# final-project.net
KiCad netlist of a schematic drawn in Altium Designer
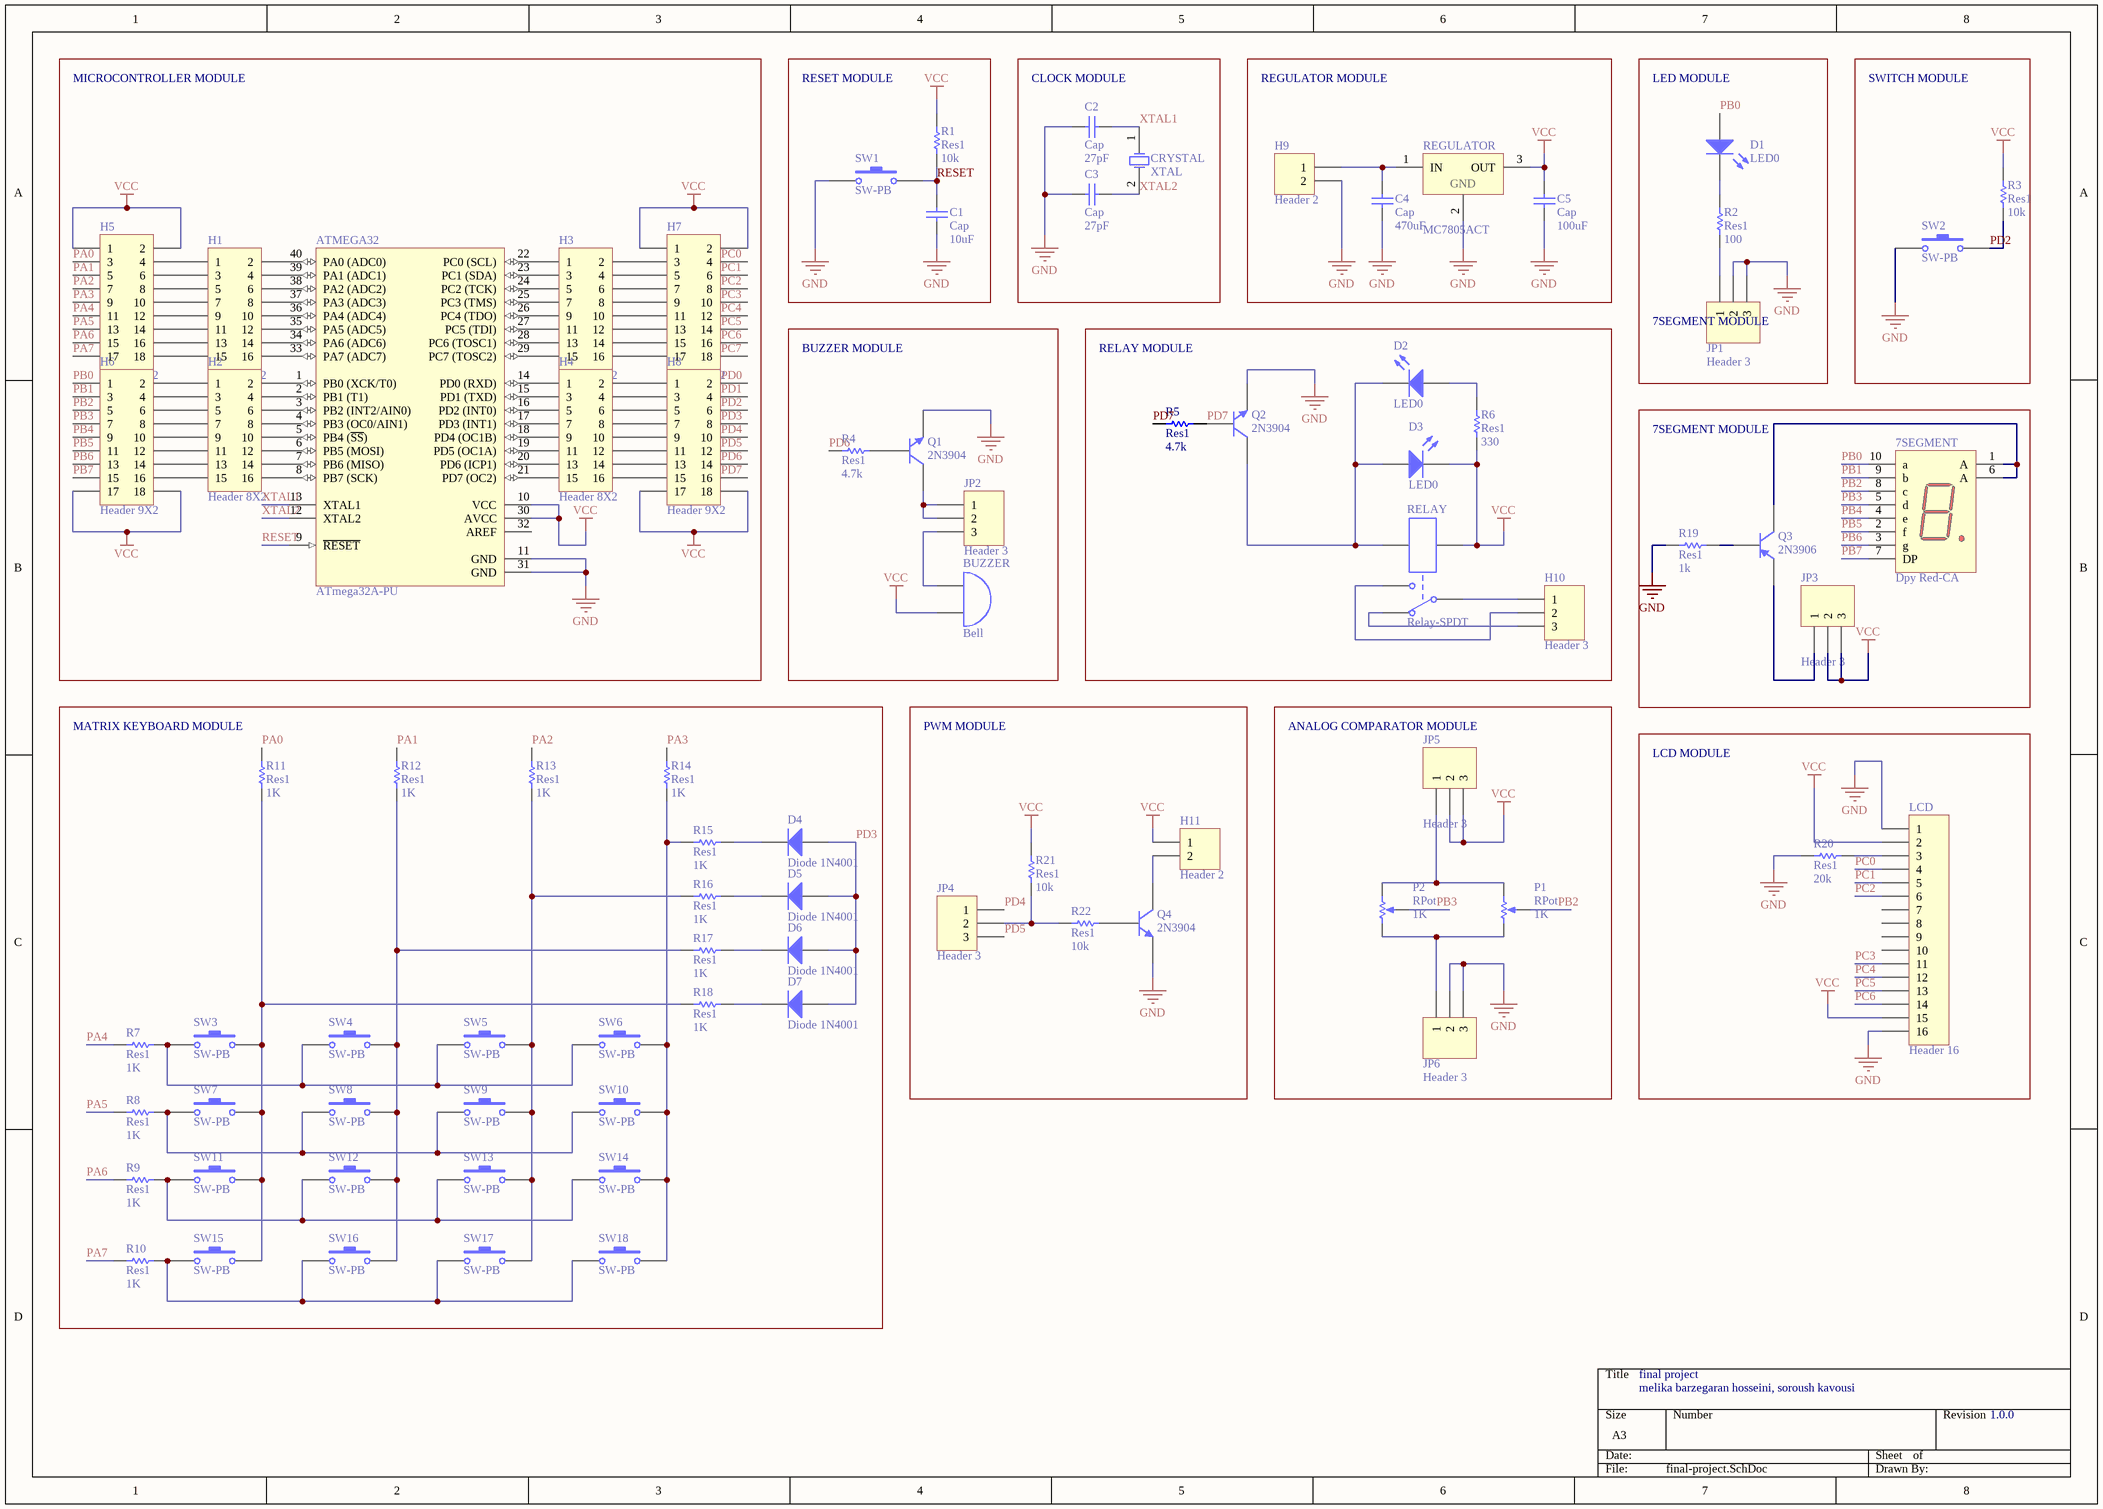
[diagram p0: final-project.SchDoc]

(export (version "E")
  (design (tool "Eeschema 10.0.6"))
  (components
    (comp (ref "7SEGMENT")
      (value "Dpy Red-CA")
      (footprint "LEDDIP-10/C5.08RHD")
      (description "7.62 mm Black Surface HER 7-Segment Display: CA, RH DP")
      (libsource (lib "Miscellaneous Devices") (part "Dpy Red-CA"))
    )
    (comp (ref "ATMEGA32")
      (value "ATmega32A-PU")
      (footprint "40P6")
      (libsource (lib "Atmel Microcontroller 8-Bit megaAVR") (part "ATmega32A-PU"))
    )
    (comp (ref "BUZZER")
      (value "Bell")
      (footprint "PIN2")
      (description "Electrical Bell")
      (libsource (lib "Miscellaneous Devices") (part "Bell"))
    )
    (comp (ref "C1")
      (value "Cap")
      (footprint "RAD-0.3")
      (description "Capacitor")
      (fields (field (name "ALTIUM_VALUE") "10uF"))
      (libsource (lib "Miscellaneous Devices") (part "Cap"))
    )
    (comp (ref "C2")
      (value "Cap")
      (footprint "RAD-0.3")
      (description "Capacitor")
      (fields (field (name "ALTIUM_VALUE") "27pF"))
      (libsource (lib "Miscellaneous Devices") (part "Cap"))
    )
    (comp (ref "C3")
      (value "Cap")
      (footprint "RAD-0.3")
      (description "Capacitor")
      (fields (field (name "ALTIUM_VALUE") "27pF"))
      (libsource (lib "Miscellaneous Devices") (part "Cap"))
    )
    (comp (ref "C4")
      (value "Cap")
      (footprint "RAD-0.3")
      (description "Capacitor")
      (fields (field (name "ALTIUM_VALUE") "470uF"))
      (libsource (lib "Miscellaneous Devices") (part "Cap"))
    )
    (comp (ref "C5")
      (value "Cap")
      (footprint "RAD-0.3")
      (description "Capacitor")
      (fields (field (name "ALTIUM_VALUE") "100uF"))
      (libsource (lib "Miscellaneous Devices") (part "Cap"))
    )
    (comp (ref "CRYSTAL")
      (value "XTAL")
      (footprint "BCY-W2/D3.1")
      (description "Crystal Oscillator")
      (libsource (lib "Miscellaneous Devices") (part "XTAL"))
    )
    (comp (ref "D1")
      (value "LED0")
      (footprint "RB5-10.5")
      (description "Typical INFRARED GaAs LED")
      (libsource (lib "Miscellaneous Devices") (part "LED0"))
    )
    (comp (ref "D2")
      (value "LED0")
      (footprint "RB5-10.5")
      (description "Typical INFRARED GaAs LED")
      (libsource (lib "Miscellaneous Devices") (part "LED0"))
    )
    (comp (ref "D3")
      (value "LED0")
      (footprint "RB5-10.5")
      (description "Typical INFRARED GaAs LED")
      (libsource (lib "Miscellaneous Devices") (part "LED0"))
    )
    (comp (ref "D4")
      (value "Diode 1N4001")
      (footprint "DIO10.46-5.3x2.8")
      (description "1 Amp General Purpose Rectifier")
      (libsource (lib "Miscellaneous Devices") (part "Diode 1N4001"))
    )
    (comp (ref "D5")
      (value "Diode 1N4001")
      (footprint "DIO10.46-5.3x2.8")
      (description "1 Amp General Purpose Rectifier")
      (libsource (lib "Miscellaneous Devices") (part "Diode 1N4001"))
    )
    (comp (ref "D6")
      (value "Diode 1N4001")
      (footprint "DIO10.46-5.3x2.8")
      (description "1 Amp General Purpose Rectifier")
      (libsource (lib "Miscellaneous Devices") (part "Diode 1N4001"))
    )
    (comp (ref "D7")
      (value "Diode 1N4001")
      (footprint "DIO10.46-5.3x2.8")
      (description "1 Amp General Purpose Rectifier")
      (libsource (lib "Miscellaneous Devices") (part "Diode 1N4001"))
    )
    (comp (ref "H1")
      (value "Header 8X2")
      (footprint "HDR1X8")
      (description "Header, 8-Pin, Dual row")
      (libsource (lib "Miscellaneous Connectors") (part "Header 8X2"))
    )
    (comp (ref "H2")
      (value "Header 8X2")
      (footprint "HDR1X8")
      (description "Header, 8-Pin, Dual row")
      (libsource (lib "Miscellaneous Connectors") (part "Header 8X2"))
    )
    (comp (ref "H3")
      (value "Header 8X2")
      (footprint "HDR1X8")
      (description "Header, 8-Pin, Dual row")
      (libsource (lib "Miscellaneous Connectors") (part "Header 8X2"))
    )
    (comp (ref "H4")
      (value "Header 8X2")
      (footprint "HDR1X8")
      (description "Header, 8-Pin, Dual row")
      (libsource (lib "Miscellaneous Connectors") (part "Header 8X2"))
    )
    (comp (ref "H5")
      (value "Header 9X2")
      (footprint "HDR1X9")
      (description "Header, 9-Pin, Dual row")
      (libsource (lib "Miscellaneous Connectors") (part "Header 9X2"))
    )
    (comp (ref "H6")
      (value "Header 9X2")
      (footprint "HDR1X9")
      (description "Header, 9-Pin, Dual row")
      (libsource (lib "Miscellaneous Connectors") (part "Header 9X2"))
    )
    (comp (ref "H7")
      (value "Header 9X2")
      (footprint "HDR1X9")
      (description "Header, 9-Pin, Dual row")
      (libsource (lib "Miscellaneous Connectors") (part "Header 9X2"))
    )
    (comp (ref "H8")
      (value "Header 9X2")
      (footprint "HDR1X9")
      (description "Header, 9-Pin, Dual row")
      (libsource (lib "Miscellaneous Connectors") (part "Header 9X2"))
    )
    (comp (ref "H9")
      (value "Header 2")
      (footprint "HDR1X2")
      (description "Header, 2-Pin")
      (libsource (lib "") (part "Header 2_1"))
    )
    (comp (ref "H10")
      (value "Header 3")
      (footprint "HDR1X3")
      (description "Header, 3-Pin")
      (libsource (lib "") (part "Header 3_2"))
    )
    (comp (ref "H11")
      (value "Header 2")
      (footprint "HDR1X2")
      (description "Header, 2-Pin")
      (libsource (lib "Miscellaneous Connectors") (part "Header 2"))
    )
    (comp (ref "JP1")
      (value "Header 3")
      (footprint "HDR1X3")
      (description "Header, 3-Pin")
      (libsource (lib "Miscellaneous Connectors") (part "Header 3"))
    )
    (comp (ref "JP2")
      (value "Header 3")
      (footprint "HDR1X3")
      (description "Header, 3-Pin")
      (libsource (lib "") (part "Header 3_2"))
    )
    (comp (ref "JP3")
      (value "Header 3")
      (footprint "HDR1X3")
      (description "Header, 3-Pin")
      (libsource (lib "") (part "Header 3_1"))
    )
    (comp (ref "JP4")
      (value "Header 3")
      (footprint "HDR1X3")
      (description "Header, 3-Pin")
      (libsource (lib "") (part "Header 3_3"))
    )
    (comp (ref "JP5")
      (value "Header 3")
      (footprint "HDR1X3")
      (description "Header, 3-Pin")
      (libsource (lib "") (part "Header 3_1"))
    )
    (comp (ref "JP6")
      (value "Header 3")
      (footprint "HDR1X3")
      (description "Header, 3-Pin")
      (libsource (lib "Miscellaneous Connectors") (part "Header 3"))
    )
    (comp (ref "LCD")
      (value "Header 16")
      (footprint "HDR1X16")
      (description "Header, 16-Pin")
      (libsource (lib "Miscellaneous Connectors") (part "Header 16"))
    )
    (comp (ref "P1")
      (value "RPot")
      (footprint "VR5")
      (description "Potentiometer")
      (fields (field (name "ALTIUM_VALUE") "1K"))
      (libsource (lib "Miscellaneous Devices") (part "RPot"))
    )
    (comp (ref "P2")
      (value "RPot")
      (footprint "VR5")
      (description "Potentiometer")
      (fields (field (name "ALTIUM_VALUE") "1K"))
      (libsource (lib "Miscellaneous Devices") (part "RPot"))
    )
    (comp (ref "Q1")
      (value "2N3904")
      (footprint "HDR1X3")
      (description "NPN General Purpose Amplifier")
      (libsource (lib "Miscellaneous Devices") (part "2N3904"))
    )
    (comp (ref "Q2")
      (value "2N3904")
      (footprint "HDR1X3")
      (description "NPN General Purpose Amplifier")
      (libsource (lib "Miscellaneous Devices") (part "2N3904"))
    )
    (comp (ref "Q3")
      (value "2N3906")
      (footprint "HDR1X3")
      (description "PNP General Purpose Amplifier")
      (libsource (lib "Miscellaneous Devices") (part "2N3906"))
    )
    (comp (ref "Q4")
      (value "2N3904")
      (footprint "HDR1X3")
      (description "NPN General Purpose Amplifier")
      (libsource (lib "Miscellaneous Devices") (part "2N3904"))
    )
    (comp (ref "R1")
      (value "Res1")
      (footprint "AXIAL-0.3")
      (description "Resistor")
      (fields (field (name "ALTIUM_VALUE") "10k"))
      (libsource (lib "Miscellaneous Devices") (part "Res1"))
    )
    (comp (ref "R2")
      (value "Res1")
      (footprint "AXIAL-0.3")
      (description "Resistor")
      (fields (field (name "ALTIUM_VALUE") "100"))
      (libsource (lib "Miscellaneous Devices") (part "Res1"))
    )
    (comp (ref "R3")
      (value "Res1")
      (footprint "AXIAL-0.3")
      (description "Resistor")
      (fields (field (name "ALTIUM_VALUE") "10k"))
      (libsource (lib "Miscellaneous Devices") (part "Res1"))
    )
    (comp (ref "R4")
      (value "Res1")
      (footprint "AXIAL-0.3")
      (description "Resistor")
      (fields (field (name "ALTIUM_VALUE") "4.7k"))
      (libsource (lib "Miscellaneous Devices") (part "Res1"))
    )
    (comp (ref "R5")
      (value "Res1")
      (footprint "AXIAL-0.3")
      (description "Resistor")
      (fields (field (name "ALTIUM_VALUE") "4.7k"))
      (libsource (lib "Miscellaneous Devices") (part "Res1"))
    )
    (comp (ref "R6")
      (value "Res1")
      (footprint "AXIAL-0.3")
      (description "Resistor")
      (fields (field (name "ALTIUM_VALUE") "330"))
      (libsource (lib "Miscellaneous Devices") (part "Res1"))
    )
    (comp (ref "R7")
      (value "Res1")
      (footprint "AXIAL-0.3")
      (description "Resistor")
      (fields (field (name "ALTIUM_VALUE") "1K"))
      (libsource (lib "Miscellaneous Devices") (part "Res1"))
    )
    (comp (ref "R8")
      (value "Res1")
      (footprint "AXIAL-0.3")
      (description "Resistor")
      (fields (field (name "ALTIUM_VALUE") "1K"))
      (libsource (lib "Miscellaneous Devices") (part "Res1"))
    )
    (comp (ref "R9")
      (value "Res1")
      (footprint "AXIAL-0.3")
      (description "Resistor")
      (fields (field (name "ALTIUM_VALUE") "1K"))
      (libsource (lib "Miscellaneous Devices") (part "Res1"))
    )
    (comp (ref "R10")
      (value "Res1")
      (footprint "AXIAL-0.3")
      (description "Resistor")
      (fields (field (name "ALTIUM_VALUE") "1K"))
      (libsource (lib "Miscellaneous Devices") (part "Res1"))
    )
    (comp (ref "R11")
      (value "Res1")
      (footprint "AXIAL-0.3")
      (description "Resistor")
      (fields (field (name "ALTIUM_VALUE") "1K"))
      (libsource (lib "Miscellaneous Devices") (part "Res1"))
    )
    (comp (ref "R12")
      (value "Res1")
      (footprint "AXIAL-0.3")
      (description "Resistor")
      (fields (field (name "ALTIUM_VALUE") "1K"))
      (libsource (lib "Miscellaneous Devices") (part "Res1"))
    )
    (comp (ref "R13")
      (value "Res1")
      (footprint "AXIAL-0.3")
      (description "Resistor")
      (fields (field (name "ALTIUM_VALUE") "1K"))
      (libsource (lib "Miscellaneous Devices") (part "Res1"))
    )
    (comp (ref "R14")
      (value "Res1")
      (footprint "AXIAL-0.3")
      (description "Resistor")
      (fields (field (name "ALTIUM_VALUE") "1K"))
      (libsource (lib "Miscellaneous Devices") (part "Res1"))
    )
    (comp (ref "R15")
      (value "Res1")
      (footprint "AXIAL-0.3")
      (description "Resistor")
      (fields (field (name "ALTIUM_VALUE") "1K"))
      (libsource (lib "Miscellaneous Devices") (part "Res1"))
    )
    (comp (ref "R16")
      (value "Res1")
      (footprint "AXIAL-0.3")
      (description "Resistor")
      (fields (field (name "ALTIUM_VALUE") "1K"))
      (libsource (lib "Miscellaneous Devices") (part "Res1"))
    )
    (comp (ref "R17")
      (value "Res1")
      (footprint "AXIAL-0.3")
      (description "Resistor")
      (fields (field (name "ALTIUM_VALUE") "1K"))
      (libsource (lib "Miscellaneous Devices") (part "Res1"))
    )
    (comp (ref "R18")
      (value "Res1")
      (footprint "AXIAL-0.3")
      (description "Resistor")
      (fields (field (name "ALTIUM_VALUE") "1K"))
      (libsource (lib "Miscellaneous Devices") (part "Res1"))
    )
    (comp (ref "R19")
      (value "Res1")
      (footprint "AXIAL-0.3")
      (description "Resistor")
      (fields (field (name "ALTIUM_VALUE") "1k"))
      (libsource (lib "Miscellaneous Devices") (part "Res1"))
    )
    (comp (ref "R20")
      (value "Res1")
      (footprint "AXIAL-0.3")
      (description "Resistor")
      (fields (field (name "ALTIUM_VALUE") "20k"))
      (libsource (lib "Miscellaneous Devices") (part "Res1"))
    )
    (comp (ref "R21")
      (value "Res1")
      (footprint "AXIAL-0.3")
      (description "Resistor")
      (fields (field (name "ALTIUM_VALUE") "10k"))
      (libsource (lib "Miscellaneous Devices") (part "Res1"))
    )
    (comp (ref "R22")
      (value "Res1")
      (footprint "AXIAL-0.3")
      (description "Resistor")
      (fields (field (name "ALTIUM_VALUE") "10k"))
      (libsource (lib "Miscellaneous Devices") (part "Res1"))
    )
    (comp (ref "REGULATOR")
      (value "MC7805ACT")
      (footprint "221A-04")
      (description "3-Terminal Positive Fixed Voltage Regulator")
      (libsource (lib "Motorola Power Mgt Voltage Regulator") (part "MC7805ACT"))
    )
    (comp (ref "RELAY")
      (value "Relay-SPDT")
      (footprint "DIP-P5/X1.65")
      (description "Single-Pole Dual-Throw Relay")
      (libsource (lib "Miscellaneous Devices") (part "Relay-SPDT"))
    )
    (comp (ref "SW1")
      (value "SW-PB")
      (footprint "SPST-2")
      (description "Switch")
      (libsource (lib "Miscellaneous Devices") (part "SW-PB"))
    )
    (comp (ref "SW2")
      (value "SW-PB")
      (footprint "SPST-2")
      (description "Switch")
      (libsource (lib "Miscellaneous Devices") (part "SW-PB"))
    )
    (comp (ref "SW3")
      (value "SW-PB")
      (footprint "SPST-2")
      (description "Switch")
      (libsource (lib "Miscellaneous Devices") (part "SW-PB"))
    )
    (comp (ref "SW4")
      (value "SW-PB")
      (footprint "SPST-2")
      (description "Switch")
      (libsource (lib "Miscellaneous Devices") (part "SW-PB"))
    )
    (comp (ref "SW5")
      (value "SW-PB")
      (footprint "SPST-2")
      (description "Switch")
      (libsource (lib "Miscellaneous Devices") (part "SW-PB"))
    )
    (comp (ref "SW6")
      (value "SW-PB")
      (footprint "SPST-2")
      (description "Switch")
      (libsource (lib "Miscellaneous Devices") (part "SW-PB"))
    )
    (comp (ref "SW7")
      (value "SW-PB")
      (footprint "SPST-2")
      (description "Switch")
      (libsource (lib "Miscellaneous Devices") (part "SW-PB"))
    )
    (comp (ref "SW8")
      (value "SW-PB")
      (footprint "SPST-2")
      (description "Switch")
      (libsource (lib "Miscellaneous Devices") (part "SW-PB"))
    )
    (comp (ref "SW9")
      (value "SW-PB")
      (footprint "SPST-2")
      (description "Switch")
      (libsource (lib "Miscellaneous Devices") (part "SW-PB"))
    )
    (comp (ref "SW10")
      (value "SW-PB")
      (footprint "SPST-2")
      (description "Switch")
      (libsource (lib "Miscellaneous Devices") (part "SW-PB"))
    )
    (comp (ref "SW11")
      (value "SW-PB")
      (footprint "SPST-2")
      (description "Switch")
      (libsource (lib "Miscellaneous Devices") (part "SW-PB"))
    )
    (comp (ref "SW12")
      (value "SW-PB")
      (footprint "SPST-2")
      (description "Switch")
      (libsource (lib "Miscellaneous Devices") (part "SW-PB"))
    )
    (comp (ref "SW13")
      (value "SW-PB")
      (footprint "SPST-2")
      (description "Switch")
      (libsource (lib "Miscellaneous Devices") (part "SW-PB"))
    )
    (comp (ref "SW14")
      (value "SW-PB")
      (footprint "SPST-2")
      (description "Switch")
      (libsource (lib "Miscellaneous Devices") (part "SW-PB"))
    )
    (comp (ref "SW15")
      (value "SW-PB")
      (footprint "SPST-2")
      (description "Switch")
      (libsource (lib "Miscellaneous Devices") (part "SW-PB"))
    )
    (comp (ref "SW16")
      (value "SW-PB")
      (footprint "SPST-2")
      (description "Switch")
      (libsource (lib "Miscellaneous Devices") (part "SW-PB"))
    )
    (comp (ref "SW17")
      (value "SW-PB")
      (footprint "SPST-2")
      (description "Switch")
      (libsource (lib "Miscellaneous Devices") (part "SW-PB"))
    )
    (comp (ref "SW18")
      (value "SW-PB")
      (footprint "SPST-2")
      (description "Switch")
      (libsource (lib "Miscellaneous Devices") (part "SW-PB"))
    )
  )
  (nets
    (net (code "1") (name "/PA0") (class "Default")
      (node (ref "H5") (pin "3") (pinfunction "3_3") (pintype "passive"))
      (node (ref "R11") (pin "2") (pinfunction "2_2") (pintype "passive"))
    )
    (net (code "2") (name "/PA1") (class "Default")
      (node (ref "H5") (pin "5") (pinfunction "5_5") (pintype "passive"))
      (node (ref "R12") (pin "2") (pinfunction "2_2") (pintype "passive"))
    )
    (net (code "3") (name "/PA2") (class "Default")
      (node (ref "H5") (pin "7") (pinfunction "7_7") (pintype "passive"))
      (node (ref "R13") (pin "2") (pinfunction "2_2") (pintype "passive"))
    )
    (net (code "4") (name "/PA3") (class "Default")
      (node (ref "H5") (pin "9") (pinfunction "9_9") (pintype "passive"))
      (node (ref "R14") (pin "2") (pinfunction "2_2") (pintype "passive"))
    )
    (net (code "5") (name "/PA4") (class "Default")
      (node (ref "H5") (pin "11") (pinfunction "11_11") (pintype "passive"))
      (node (ref "R7") (pin "1") (pinfunction "1_1") (pintype "passive"))
    )
    (net (code "6") (name "/PA5") (class "Default")
      (node (ref "H5") (pin "13") (pinfunction "13_13") (pintype "passive"))
      (node (ref "R8") (pin "1") (pinfunction "1_1") (pintype "passive"))
    )
    (net (code "7") (name "/PA6") (class "Default")
      (node (ref "H5") (pin "15") (pinfunction "15_15") (pintype "passive"))
      (node (ref "R9") (pin "1") (pinfunction "1_1") (pintype "passive"))
    )
    (net (code "8") (name "/PA7") (class "Default")
      (node (ref "H5") (pin "17") (pinfunction "17_17") (pintype "passive"))
      (node (ref "R10") (pin "1") (pinfunction "1_1") (pintype "passive"))
    )
    (net (code "9") (name "/PB0") (class "Default")
      (node (ref "7SEGMENT") (pin "10") (pinfunction "a_10") (pintype "passive"))
      (node (ref "D1") (pin "1") (pinfunction "A_1") (pintype "passive"))
      (node (ref "H6") (pin "1") (pinfunction "1_1") (pintype "passive"))
    )
    (net (code "10") (name "/PB1") (class "Default")
      (node (ref "7SEGMENT") (pin "9") (pinfunction "b_9") (pintype "passive"))
      (node (ref "H6") (pin "3") (pinfunction "3_3") (pintype "passive"))
    )
    (net (code "11") (name "/PB2") (class "Default")
      (node (ref "7SEGMENT") (pin "8") (pinfunction "c_8") (pintype "passive"))
      (node (ref "H6") (pin "5") (pinfunction "5_5") (pintype "passive"))
      (node (ref "P1") (pin "3") (pinfunction "TAP_3") (pintype "passive"))
    )
    (net (code "12") (name "/PB3") (class "Default")
      (node (ref "7SEGMENT") (pin "5") (pinfunction "d_5") (pintype "passive"))
      (node (ref "H6") (pin "7") (pinfunction "7_7") (pintype "passive"))
      (node (ref "P2") (pin "3") (pinfunction "TAP_3") (pintype "passive"))
    )
    (net (code "13") (name "/PB4") (class "Default")
      (node (ref "7SEGMENT") (pin "4") (pinfunction "e_4") (pintype "passive"))
      (node (ref "H6") (pin "9") (pinfunction "9_9") (pintype "passive"))
    )
    (net (code "14") (name "/PB5") (class "Default")
      (node (ref "7SEGMENT") (pin "2") (pinfunction "f_2") (pintype "passive"))
      (node (ref "H6") (pin "11") (pinfunction "11_11") (pintype "passive"))
    )
    (net (code "15") (name "/PB6") (class "Default")
      (node (ref "7SEGMENT") (pin "3") (pinfunction "g_3") (pintype "passive"))
      (node (ref "H6") (pin "13") (pinfunction "13_13") (pintype "passive"))
    )
    (net (code "16") (name "/PB7") (class "Default")
      (node (ref "7SEGMENT") (pin "7") (pinfunction "DP_7") (pintype "passive"))
      (node (ref "H6") (pin "15") (pinfunction "15_15") (pintype "passive"))
    )
    (net (code "17") (name "/PC0") (class "Default")
      (node (ref "LCD") (pin "4") (pinfunction "4_4") (pintype "passive"))
    )
    (net (code "18") (name "/PC1") (class "Default")
      (node (ref "LCD") (pin "5") (pinfunction "5_5") (pintype "passive"))
    )
    (net (code "19") (name "/PC2") (class "Default")
      (node (ref "LCD") (pin "6") (pinfunction "6_6") (pintype "passive"))
    )
    (net (code "20") (name "/PC3") (class "Default")
      (node (ref "LCD") (pin "11") (pinfunction "11_11") (pintype "passive"))
    )
    (net (code "21") (name "/PC4") (class "Default")
      (node (ref "LCD") (pin "12") (pinfunction "12_12") (pintype "passive"))
    )
    (net (code "22") (name "/PC5") (class "Default")
      (node (ref "LCD") (pin "13") (pinfunction "13_13") (pintype "passive"))
    )
    (net (code "23") (name "/PC6") (class "Default")
      (node (ref "LCD") (pin "14") (pinfunction "14_14") (pintype "passive"))
    )
    (net (code "27") (name "/PD2") (class "Default")
      (node (ref "R3") (pin "1") (pinfunction "1_1") (pintype "passive"))
      (node (ref "SW2") (pin "2") (pinfunction "2_2") (pintype "passive"))
    )
    (net (code "28") (name "/PD3") (class "Default")
      (node (ref "D4") (pin "1") (pinfunction "A_1") (pintype "passive"))
      (node (ref "D5") (pin "1") (pinfunction "A_1") (pintype "passive"))
      (node (ref "D6") (pin "1") (pinfunction "A_1") (pintype "passive"))
      (node (ref "D7") (pin "1") (pinfunction "A_1") (pintype "passive"))
    )
    (net (code "29") (name "/PD4") (class "Default")
      (node (ref "JP4") (pin "1") (pinfunction "1_1") (pintype "passive"))
    )
    (net (code "30") (name "/PD5") (class "Default")
      (node (ref "JP4") (pin "3") (pinfunction "3_3") (pintype "passive"))
    )
    (net (code "31") (name "/PD6") (class "Default")
      (node (ref "R4") (pin "1") (pinfunction "1_1") (pintype "passive"))
    )
    (net (code "32") (name "/PD7") (class "Default")
      (node (ref "Q2") (pin "2") (pinfunction "B_2") (pintype "passive"))
      (node (ref "R5") (pin "1") (pinfunction "1_1") (pintype "passive"))
      (node (ref "R5") (pin "2") (pinfunction "2_2") (pintype "passive"))
    )
    (net (code "33") (name "/RESET") (class "Default")
      (node (ref "ATMEGA32") (pin "9") (pinfunction "~{RESET}_9") (pintype "input"))
      (node (ref "C1") (pin "2") (pinfunction "2_2") (pintype "passive"))
      (node (ref "R1") (pin "1") (pinfunction "1_1") (pintype "passive"))
      (node (ref "SW1") (pin "2") (pinfunction "2_2") (pintype "passive"))
    )
    (net (code "34") (name "/XTAL1") (class "Default")
      (node (ref "ATMEGA32") (pin "13") (pinfunction "XTAL1_13") (pintype "passive"))
      (node (ref "C2") (pin "2") (pinfunction "2_2") (pintype "passive"))
      (node (ref "CRYSTAL") (pin "1") (pinfunction "OSC1_1") (pintype "passive"))
    )
    (net (code "35") (name "/XTAL2") (class "Default")
      (node (ref "ATMEGA32") (pin "12") (pinfunction "XTAL2_12") (pintype "passive"))
      (node (ref "C3") (pin "2") (pinfunction "2_2") (pintype "passive"))
      (node (ref "CRYSTAL") (pin "2") (pinfunction "OSC2_2") (pintype "passive"))
    )
    (net (code "36") (name "GND") (class "Default")
      (node (ref "ATMEGA32") (pin "11") (pinfunction "GND_11") (pintype "power_in"))
      (node (ref "ATMEGA32") (pin "31") (pinfunction "GND_31") (pintype "power_in"))
      (node (ref "C1") (pin "1") (pinfunction "1_1") (pintype "passive"))
      (node (ref "C2") (pin "1") (pinfunction "1_1") (pintype "passive"))
      (node (ref "C3") (pin "1") (pinfunction "1_1") (pintype "passive"))
      (node (ref "C4") (pin "1") (pinfunction "1_1") (pintype "passive"))
      (node (ref "C5") (pin "1") (pinfunction "1_1") (pintype "passive"))
      (node (ref "H9") (pin "2") (pinfunction "2_2") (pintype "passive"))
      (node (ref "JP1") (pin "2") (pinfunction "2_2") (pintype "passive"))
      (node (ref "JP1") (pin "3") (pinfunction "3_3") (pintype "passive"))
      (node (ref "JP6") (pin "2") (pinfunction "2_2") (pintype "passive"))
      (node (ref "JP6") (pin "3") (pinfunction "3_3") (pintype "passive"))
      (node (ref "LCD") (pin "1") (pinfunction "1_1") (pintype "passive"))
      (node (ref "LCD") (pin "16") (pinfunction "16_16") (pintype "passive"))
      (node (ref "Q1") (pin "1") (pinfunction "E_1") (pintype "passive"))
      (node (ref "Q2") (pin "1") (pinfunction "E_1") (pintype "passive"))
      (node (ref "Q4") (pin "1") (pinfunction "E_1") (pintype "passive"))
      (node (ref "R19") (pin "1") (pinfunction "1_1") (pintype "passive"))
      (node (ref "R20") (pin "1") (pinfunction "1_1") (pintype "passive"))
      (node (ref "REGULATOR") (pin "2") (pinfunction "GND_2") (pintype "power_in"))
      (node (ref "SW1") (pin "1") (pinfunction "1_1") (pintype "passive"))
      (node (ref "SW2") (pin "1") (pinfunction "1_1") (pintype "passive"))
    )
    (net (code "37") (name "Net-(ATMEGA32-PA0_(ADC0))") (class "Default")
      (node (ref "ATMEGA32") (pin "40") (pinfunction "PA0_(ADC0)_40") (pintype "bidirectional"))
      (node (ref "H1") (pin "2") (pinfunction "2_2") (pintype "passive"))
    )
    (net (code "38") (name "Net-(ATMEGA32-PA1_(ADC1))") (class "Default")
      (node (ref "ATMEGA32") (pin "39") (pinfunction "PA1_(ADC1)_39") (pintype "bidirectional"))
      (node (ref "H1") (pin "4") (pinfunction "4_4") (pintype "passive"))
    )
    (net (code "39") (name "Net-(ATMEGA32-PA2_(ADC2))") (class "Default")
      (node (ref "ATMEGA32") (pin "38") (pinfunction "PA2_(ADC2)_38") (pintype "bidirectional"))
      (node (ref "H1") (pin "6") (pinfunction "6_6") (pintype "passive"))
    )
    (net (code "40") (name "Net-(ATMEGA32-PA3_(ADC3))") (class "Default")
      (node (ref "ATMEGA32") (pin "37") (pinfunction "PA3_(ADC3)_37") (pintype "bidirectional"))
      (node (ref "H1") (pin "8") (pinfunction "8_8") (pintype "passive"))
    )
    (net (code "41") (name "Net-(ATMEGA32-PA4_(ADC4))") (class "Default")
      (node (ref "ATMEGA32") (pin "36") (pinfunction "PA4_(ADC4)_36") (pintype "bidirectional"))
      (node (ref "H1") (pin "10") (pinfunction "10_10") (pintype "passive"))
    )
    (net (code "42") (name "Net-(ATMEGA32-PA5_(ADC5))") (class "Default")
      (node (ref "ATMEGA32") (pin "35") (pinfunction "PA5_(ADC5)_35") (pintype "bidirectional"))
      (node (ref "H1") (pin "12") (pinfunction "12_12") (pintype "passive"))
    )
    (net (code "43") (name "Net-(ATMEGA32-PA6_(ADC6))") (class "Default")
      (node (ref "ATMEGA32") (pin "34") (pinfunction "PA6_(ADC6)_34") (pintype "bidirectional"))
      (node (ref "H1") (pin "14") (pinfunction "14_14") (pintype "passive"))
    )
    (net (code "44") (name "Net-(ATMEGA32-PA7_(ADC7))") (class "Default")
      (node (ref "ATMEGA32") (pin "33") (pinfunction "PA7_(ADC7)_33") (pintype "bidirectional"))
      (node (ref "H1") (pin "16") (pinfunction "16_16") (pintype "passive"))
    )
    (net (code "45") (name "Net-(ATMEGA32-PB0_(XCK{slash}T0))") (class "Default")
      (node (ref "ATMEGA32") (pin "1") (pinfunction "PB0_(XCK/T0)_1") (pintype "bidirectional"))
      (node (ref "H2") (pin "2") (pinfunction "2_2") (pintype "passive"))
    )
    (net (code "46") (name "Net-(ATMEGA32-PB1_(T1))") (class "Default")
      (node (ref "ATMEGA32") (pin "2") (pinfunction "PB1_(T1)_2") (pintype "bidirectional"))
      (node (ref "H2") (pin "4") (pinfunction "4_4") (pintype "passive"))
    )
    (net (code "47") (name "Net-(ATMEGA32-PB2_(INT2{slash}AIN0))") (class "Default")
      (node (ref "ATMEGA32") (pin "3") (pinfunction "PB2_(INT2/AIN0)_3") (pintype "bidirectional"))
      (node (ref "H2") (pin "6") (pinfunction "6_6") (pintype "passive"))
    )
    (net (code "48") (name "Net-(ATMEGA32-PB3_(OC0{slash}AIN1))") (class "Default")
      (node (ref "ATMEGA32") (pin "4") (pinfunction "PB3_(OC0/AIN1)_4") (pintype "bidirectional"))
      (node (ref "H2") (pin "8") (pinfunction "8_8") (pintype "passive"))
    )
    (net (code "49") (name "Net-(ATMEGA32-PB4_(~{SS}))") (class "Default")
      (node (ref "ATMEGA32") (pin "5") (pinfunction "PB4_(~{SS})_5") (pintype "bidirectional"))
      (node (ref "H2") (pin "10") (pinfunction "10_10") (pintype "passive"))
    )
    (net (code "50") (name "Net-(ATMEGA32-PB5_(MOSI))") (class "Default")
      (node (ref "ATMEGA32") (pin "6") (pinfunction "PB5_(MOSI)_6") (pintype "bidirectional"))
      (node (ref "H2") (pin "12") (pinfunction "12_12") (pintype "passive"))
    )
    (net (code "51") (name "Net-(ATMEGA32-PB6_(MISO))") (class "Default")
      (node (ref "ATMEGA32") (pin "7") (pinfunction "PB6_(MISO)_7") (pintype "bidirectional"))
      (node (ref "H2") (pin "14") (pinfunction "14_14") (pintype "passive"))
    )
    (net (code "52") (name "Net-(ATMEGA32-PB7_(SCK))") (class "Default")
      (node (ref "ATMEGA32") (pin "8") (pinfunction "PB7_(SCK)_8") (pintype "bidirectional"))
      (node (ref "H2") (pin "16") (pinfunction "16_16") (pintype "passive"))
    )
    (net (code "53") (name "Net-(ATMEGA32-PC0_(SCL))") (class "Default")
      (node (ref "ATMEGA32") (pin "22") (pinfunction "PC0_(SCL)_22") (pintype "bidirectional"))
      (node (ref "H3") (pin "1") (pinfunction "1_1") (pintype "passive"))
    )
    (net (code "54") (name "Net-(ATMEGA32-PC1_(SDA))") (class "Default")
      (node (ref "ATMEGA32") (pin "23") (pinfunction "PC1_(SDA)_23") (pintype "bidirectional"))
      (node (ref "H3") (pin "3") (pinfunction "3_3") (pintype "passive"))
    )
    (net (code "55") (name "Net-(ATMEGA32-PC2_(TCK))") (class "Default")
      (node (ref "ATMEGA32") (pin "24") (pinfunction "PC2_(TCK)_24") (pintype "bidirectional"))
      (node (ref "H3") (pin "5") (pinfunction "5_5") (pintype "passive"))
    )
    (net (code "56") (name "Net-(ATMEGA32-PC3_(TMS))") (class "Default")
      (node (ref "ATMEGA32") (pin "25") (pinfunction "PC3_(TMS)_25") (pintype "bidirectional"))
      (node (ref "H3") (pin "7") (pinfunction "7_7") (pintype "passive"))
    )
    (net (code "57") (name "Net-(ATMEGA32-PC4_(TDO))") (class "Default")
      (node (ref "ATMEGA32") (pin "26") (pinfunction "PC4_(TDO)_26") (pintype "bidirectional"))
      (node (ref "H3") (pin "9") (pinfunction "9_9") (pintype "passive"))
    )
    (net (code "58") (name "Net-(ATMEGA32-PC5_(TDI))") (class "Default")
      (node (ref "ATMEGA32") (pin "27") (pinfunction "PC5_(TDI)_27") (pintype "bidirectional"))
      (node (ref "H3") (pin "11") (pinfunction "11_11") (pintype "passive"))
    )
    (net (code "59") (name "Net-(ATMEGA32-PC6_(TOSC1))") (class "Default")
      (node (ref "ATMEGA32") (pin "28") (pinfunction "PC6_(TOSC1)_28") (pintype "bidirectional"))
      (node (ref "H3") (pin "13") (pinfunction "13_13") (pintype "passive"))
    )
    (net (code "60") (name "Net-(ATMEGA32-PC7_(TOSC2))") (class "Default")
      (node (ref "ATMEGA32") (pin "29") (pinfunction "PC7_(TOSC2)_29") (pintype "bidirectional"))
      (node (ref "H3") (pin "15") (pinfunction "15_15") (pintype "passive"))
    )
    (net (code "61") (name "Net-(ATMEGA32-PD0_(RXD))") (class "Default")
      (node (ref "ATMEGA32") (pin "14") (pinfunction "PD0_(RXD)_14") (pintype "bidirectional"))
      (node (ref "H4") (pin "1") (pinfunction "1_1") (pintype "passive"))
    )
    (net (code "62") (name "Net-(ATMEGA32-PD1_(TXD))") (class "Default")
      (node (ref "ATMEGA32") (pin "15") (pinfunction "PD1_(TXD)_15") (pintype "bidirectional"))
      (node (ref "H4") (pin "3") (pinfunction "3_3") (pintype "passive"))
    )
    (net (code "63") (name "Net-(ATMEGA32-PD2_(INT0))") (class "Default")
      (node (ref "ATMEGA32") (pin "16") (pinfunction "PD2_(INT0)_16") (pintype "bidirectional"))
      (node (ref "H4") (pin "5") (pinfunction "5_5") (pintype "passive"))
    )
    (net (code "64") (name "Net-(ATMEGA32-PD3_(INT1))") (class "Default")
      (node (ref "ATMEGA32") (pin "17") (pinfunction "PD3_(INT1)_17") (pintype "bidirectional"))
      (node (ref "H4") (pin "7") (pinfunction "7_7") (pintype "passive"))
    )
    (net (code "65") (name "Net-(ATMEGA32-PD4_(OC1B))") (class "Default")
      (node (ref "ATMEGA32") (pin "18") (pinfunction "PD4_(OC1B)_18") (pintype "bidirectional"))
      (node (ref "H4") (pin "9") (pinfunction "9_9") (pintype "passive"))
    )
    (net (code "66") (name "Net-(ATMEGA32-PD5_(OC1A))") (class "Default")
      (node (ref "ATMEGA32") (pin "19") (pinfunction "PD5_(OC1A)_19") (pintype "bidirectional"))
      (node (ref "H4") (pin "11") (pinfunction "11_11") (pintype "passive"))
    )
    (net (code "67") (name "Net-(ATMEGA32-PD6_(ICP1))") (class "Default")
      (node (ref "ATMEGA32") (pin "20") (pinfunction "PD6_(ICP1)_20") (pintype "bidirectional"))
      (node (ref "H4") (pin "13") (pinfunction "13_13") (pintype "passive"))
    )
    (net (code "68") (name "Net-(ATMEGA32-PD7_(OC2))") (class "Default")
      (node (ref "ATMEGA32") (pin "21") (pinfunction "PD7_(OC2)_21") (pintype "bidirectional"))
      (node (ref "H4") (pin "15") (pinfunction "15_15") (pintype "passive"))
    )
    (net (code "69") (name "Net-(BUZZER-A)") (class "Default")
      (node (ref "BUZZER") (pin "1") (pinfunction "A_1") (pintype "passive"))
      (node (ref "JP2") (pin "3") (pinfunction "3_3") (pintype "passive"))
    )
    (net (code "70") (name "Net-(D1-K)") (class "Default")
      (node (ref "D1") (pin "2") (pinfunction "K_2") (pintype "passive"))
      (node (ref "R2") (pin "2") (pinfunction "2_2") (pintype "passive"))
    )
    (net (code "71") (name "Net-(D2-A)") (class "Default")
      (node (ref "D2") (pin "1") (pinfunction "A_1") (pintype "passive"))
      (node (ref "R6") (pin "2") (pinfunction "2_2") (pintype "passive"))
    )
    (net (code "72") (name "Net-(D2-K)") (class "Default")
      (node (ref "D2") (pin "2") (pinfunction "K_2") (pintype "passive"))
      (node (ref "D3") (pin "1") (pinfunction "A_1") (pintype "passive"))
      (node (ref "Q2") (pin "3") (pinfunction "C_3") (pintype "passive"))
      (node (ref "RELAY") (pin "5") (pinfunction "5_5") (pintype "passive"))
    )
    (net (code "73") (name "Net-(D4-K)") (class "Default")
      (node (ref "D4") (pin "2") (pinfunction "K_2") (pintype "passive"))
      (node (ref "R15") (pin "2") (pinfunction "2_2") (pintype "passive"))
    )
    (net (code "74") (name "Net-(D5-K)") (class "Default")
      (node (ref "D5") (pin "2") (pinfunction "K_2") (pintype "passive"))
      (node (ref "R16") (pin "2") (pinfunction "2_2") (pintype "passive"))
    )
    (net (code "75") (name "Net-(D6-K)") (class "Default")
      (node (ref "D6") (pin "2") (pinfunction "K_2") (pintype "passive"))
      (node (ref "R17") (pin "2") (pinfunction "2_2") (pintype "passive"))
    )
    (net (code "76") (name "Net-(D7-K)") (class "Default")
      (node (ref "D7") (pin "2") (pinfunction "K_2") (pintype "passive"))
      (node (ref "R18") (pin "2") (pinfunction "2_2") (pintype "passive"))
    )
    (net (code "77") (name "Net-(H1-Pad1)") (class "Default")
      (node (ref "H1") (pin "1") (pinfunction "1_1") (pintype "passive"))
      (node (ref "H5") (pin "4") (pinfunction "4_4") (pintype "passive"))
    )
    (net (code "78") (name "Net-(H1-Pad3)") (class "Default")
      (node (ref "H1") (pin "3") (pinfunction "3_3") (pintype "passive"))
      (node (ref "H5") (pin "6") (pinfunction "6_6") (pintype "passive"))
    )
    (net (code "79") (name "Net-(H1-Pad5)") (class "Default")
      (node (ref "H1") (pin "5") (pinfunction "5_5") (pintype "passive"))
      (node (ref "H5") (pin "8") (pinfunction "8_8") (pintype "passive"))
    )
    (net (code "80") (name "Net-(H1-Pad7)") (class "Default")
      (node (ref "H1") (pin "7") (pinfunction "7_7") (pintype "passive"))
      (node (ref "H5") (pin "10") (pinfunction "10_10") (pintype "passive"))
    )
    (net (code "81") (name "Net-(H1-Pad9)") (class "Default")
      (node (ref "H1") (pin "9") (pinfunction "9_9") (pintype "passive"))
      (node (ref "H5") (pin "12") (pinfunction "12_12") (pintype "passive"))
    )
    (net (code "82") (name "Net-(H1-Pad11)") (class "Default")
      (node (ref "H1") (pin "11") (pinfunction "11_11") (pintype "passive"))
      (node (ref "H5") (pin "14") (pinfunction "14_14") (pintype "passive"))
    )
    (net (code "83") (name "Net-(H1-Pad13)") (class "Default")
      (node (ref "H1") (pin "13") (pinfunction "13_13") (pintype "passive"))
      (node (ref "H5") (pin "16") (pinfunction "16_16") (pintype "passive"))
    )
    (net (code "84") (name "Net-(H1-Pad15)") (class "Default")
      (node (ref "H1") (pin "15") (pinfunction "15_15") (pintype "passive"))
      (node (ref "H5") (pin "18") (pinfunction "18_18") (pintype "passive"))
    )
    (net (code "85") (name "Net-(H2-Pad1)") (class "Default")
      (node (ref "H2") (pin "1") (pinfunction "1_1") (pintype "passive"))
      (node (ref "H6") (pin "2") (pinfunction "2_2") (pintype "passive"))
    )
    (net (code "86") (name "Net-(H2-Pad3)") (class "Default")
      (node (ref "H2") (pin "3") (pinfunction "3_3") (pintype "passive"))
      (node (ref "H6") (pin "4") (pinfunction "4_4") (pintype "passive"))
    )
    (net (code "87") (name "Net-(H2-Pad5)") (class "Default")
      (node (ref "H2") (pin "5") (pinfunction "5_5") (pintype "passive"))
      (node (ref "H6") (pin "6") (pinfunction "6_6") (pintype "passive"))
    )
    (net (code "88") (name "Net-(H2-Pad7)") (class "Default")
      (node (ref "H2") (pin "7") (pinfunction "7_7") (pintype "passive"))
      (node (ref "H6") (pin "8") (pinfunction "8_8") (pintype "passive"))
    )
    (net (code "89") (name "Net-(H2-Pad9)") (class "Default")
      (node (ref "H2") (pin "9") (pinfunction "9_9") (pintype "passive"))
      (node (ref "H6") (pin "10") (pinfunction "10_10") (pintype "passive"))
    )
    (net (code "90") (name "Net-(H2-Pad11)") (class "Default")
      (node (ref "H2") (pin "11") (pinfunction "11_11") (pintype "passive"))
      (node (ref "H6") (pin "12") (pinfunction "12_12") (pintype "passive"))
    )
    (net (code "91") (name "Net-(H2-Pad13)") (class "Default")
      (node (ref "H2") (pin "13") (pinfunction "13_13") (pintype "passive"))
      (node (ref "H6") (pin "14") (pinfunction "14_14") (pintype "passive"))
    )
    (net (code "92") (name "Net-(H2-Pad15)") (class "Default")
      (node (ref "H2") (pin "15") (pinfunction "15_15") (pintype "passive"))
      (node (ref "H6") (pin "16") (pinfunction "16_16") (pintype "passive"))
    )
    (net (code "93") (name "Net-(H3-Pad2)") (class "Default")
      (node (ref "H3") (pin "2") (pinfunction "2_2") (pintype "passive"))
      (node (ref "H7") (pin "3") (pinfunction "3_3") (pintype "passive"))
    )
    (net (code "94") (name "Net-(H3-Pad4)") (class "Default")
      (node (ref "H3") (pin "4") (pinfunction "4_4") (pintype "passive"))
      (node (ref "H7") (pin "5") (pinfunction "5_5") (pintype "passive"))
    )
    (net (code "95") (name "Net-(H3-Pad6)") (class "Default")
      (node (ref "H3") (pin "6") (pinfunction "6_6") (pintype "passive"))
      (node (ref "H7") (pin "7") (pinfunction "7_7") (pintype "passive"))
    )
    (net (code "96") (name "Net-(H3-Pad8)") (class "Default")
      (node (ref "H3") (pin "8") (pinfunction "8_8") (pintype "passive"))
      (node (ref "H7") (pin "9") (pinfunction "9_9") (pintype "passive"))
    )
    (net (code "97") (name "Net-(H3-Pad10)") (class "Default")
      (node (ref "H3") (pin "10") (pinfunction "10_10") (pintype "passive"))
      (node (ref "H7") (pin "11") (pinfunction "11_11") (pintype "passive"))
    )
    (net (code "98") (name "Net-(H3-Pad12)") (class "Default")
      (node (ref "H3") (pin "12") (pinfunction "12_12") (pintype "passive"))
      (node (ref "H7") (pin "13") (pinfunction "13_13") (pintype "passive"))
    )
    (net (code "99") (name "Net-(H3-Pad14)") (class "Default")
      (node (ref "H3") (pin "14") (pinfunction "14_14") (pintype "passive"))
      (node (ref "H7") (pin "15") (pinfunction "15_15") (pintype "passive"))
    )
    (net (code "100") (name "Net-(H3-Pad16)") (class "Default")
      (node (ref "H3") (pin "16") (pinfunction "16_16") (pintype "passive"))
      (node (ref "H7") (pin "17") (pinfunction "17_17") (pintype "passive"))
    )
    (net (code "101") (name "Net-(H4-Pad2)") (class "Default")
      (node (ref "H4") (pin "2") (pinfunction "2_2") (pintype "passive"))
      (node (ref "H8") (pin "1") (pinfunction "1_1") (pintype "passive"))
    )
    (net (code "102") (name "Net-(H4-Pad4)") (class "Default")
      (node (ref "H4") (pin "4") (pinfunction "4_4") (pintype "passive"))
      (node (ref "H8") (pin "3") (pinfunction "3_3") (pintype "passive"))
    )
    (net (code "103") (name "Net-(H4-Pad6)") (class "Default")
      (node (ref "H4") (pin "6") (pinfunction "6_6") (pintype "passive"))
      (node (ref "H8") (pin "5") (pinfunction "5_5") (pintype "passive"))
    )
    (net (code "104") (name "Net-(H4-Pad8)") (class "Default")
      (node (ref "H4") (pin "8") (pinfunction "8_8") (pintype "passive"))
      (node (ref "H8") (pin "7") (pinfunction "7_7") (pintype "passive"))
    )
    (net (code "105") (name "Net-(H4-Pad10)") (class "Default")
      (node (ref "H4") (pin "10") (pinfunction "10_10") (pintype "passive"))
      (node (ref "H8") (pin "9") (pinfunction "9_9") (pintype "passive"))
    )
    (net (code "106") (name "Net-(H4-Pad12)") (class "Default")
      (node (ref "H4") (pin "12") (pinfunction "12_12") (pintype "passive"))
      (node (ref "H8") (pin "11") (pinfunction "11_11") (pintype "passive"))
    )
    (net (code "107") (name "Net-(H4-Pad14)") (class "Default")
      (node (ref "H4") (pin "14") (pinfunction "14_14") (pintype "passive"))
      (node (ref "H8") (pin "13") (pinfunction "13_13") (pintype "passive"))
    )
    (net (code "108") (name "Net-(H4-Pad16)") (class "Default")
      (node (ref "H4") (pin "16") (pinfunction "16_16") (pintype "passive"))
      (node (ref "H8") (pin "15") (pinfunction "15_15") (pintype "passive"))
    )
    (net (code "109") (name "Net-(H10-Pad1)") (class "Default")
      (node (ref "H10") (pin "1") (pinfunction "1_1") (pintype "passive"))
      (node (ref "RELAY") (pin "1") (pinfunction "1_1") (pintype "passive"))
    )
    (net (code "110") (name "Net-(H10-Pad2)") (class "Default")
      (node (ref "H10") (pin "2") (pinfunction "2_2") (pintype "passive"))
      (node (ref "RELAY") (pin "3") (pinfunction "3_3") (pintype "passive"))
    )
    (net (code "111") (name "Net-(H10-Pad3)") (class "Default")
      (node (ref "H10") (pin "3") (pinfunction "3_3") (pintype "passive"))
      (node (ref "RELAY") (pin "2") (pinfunction "2_2") (pintype "passive"))
    )
    (net (code "112") (name "Net-(JP1-Pad1)") (class "Default")
      (node (ref "JP1") (pin "1") (pinfunction "1_1") (pintype "passive"))
      (node (ref "R2") (pin "1") (pinfunction "1_1") (pintype "passive"))
    )
    (net (code "113") (name "Net-(JP4-Pad2)") (class "Default")
      (node (ref "JP4") (pin "2") (pinfunction "2_2") (pintype "passive"))
      (node (ref "R21") (pin "1") (pinfunction "1_1") (pintype "passive"))
      (node (ref "R22") (pin "1") (pinfunction "1_1") (pintype "passive"))
    )
    (net (code "114") (name "Net-(LCD-Pad3)") (class "Default")
      (node (ref "LCD") (pin "3") (pinfunction "3_3") (pintype "passive"))
      (node (ref "R20") (pin "2") (pinfunction "2_2") (pintype "passive"))
    )
    (net (code "115") (name "Net-(P1-BOT)") (class "Default")
      (node (ref "JP5") (pin "1") (pinfunction "1_1") (pintype "passive"))
      (node (ref "P1") (pin "2") (pinfunction "BOT_2") (pintype "passive"))
      (node (ref "P2") (pin "2") (pinfunction "BOT_2") (pintype "passive"))
    )
    (net (code "116") (name "Net-(P1-TOP)") (class "Default")
      (node (ref "JP6") (pin "1") (pinfunction "1_1") (pintype "passive"))
      (node (ref "P1") (pin "1") (pinfunction "TOP_1") (pintype "passive"))
      (node (ref "P2") (pin "1") (pinfunction "TOP_1") (pintype "passive"))
    )
    (net (code "117") (name "Net-(Q1-B)") (class "Default")
      (node (ref "Q1") (pin "2") (pinfunction "B_2") (pintype "passive"))
      (node (ref "R4") (pin "2") (pinfunction "2_2") (pintype "passive"))
    )
    (net (code "118") (name "Net-(Q1-C)") (class "Default")
      (node (ref "JP2") (pin "1") (pinfunction "1_1") (pintype "passive"))
      (node (ref "JP2") (pin "2") (pinfunction "2_2") (pintype "passive"))
      (node (ref "Q1") (pin "3") (pinfunction "C_3") (pintype "passive"))
    )
    (net (code "119") (name "Net-(Q3-B)") (class "Default")
      (node (ref "Q3") (pin "2") (pinfunction "B_2") (pintype "passive"))
      (node (ref "R19") (pin "2") (pinfunction "2_2") (pintype "passive"))
    )
    (net (code "120") (name "Net-(Q3-C)") (class "Default")
      (node (ref "7SEGMENT") (pin "1") (pinfunction "A_1") (pintype "passive"))
      (node (ref "7SEGMENT") (pin "6") (pinfunction "A_6") (pintype "passive"))
      (node (ref "Q3") (pin "3") (pinfunction "C_3") (pintype "passive"))
    )
    (net (code "121") (name "Net-(Q3-E)") (class "Default")
      (node (ref "JP3") (pin "1") (pinfunction "1_1") (pintype "passive"))
      (node (ref "Q3") (pin "1") (pinfunction "E_1") (pintype "passive"))
    )
    (net (code "122") (name "Net-(Q4-B)") (class "Default")
      (node (ref "Q4") (pin "2") (pinfunction "B_2") (pintype "passive"))
      (node (ref "R22") (pin "2") (pinfunction "2_2") (pintype "passive"))
    )
    (net (code "123") (name "Net-(Q4-C)") (class "Default")
      (node (ref "H11") (pin "2") (pinfunction "2_2") (pintype "passive"))
      (node (ref "Q4") (pin "3") (pinfunction "C_3") (pintype "passive"))
    )
    (net (code "124") (name "Net-(R7-Pad2)") (class "Default")
      (node (ref "R7") (pin "2") (pinfunction "2_2") (pintype "passive"))
      (node (ref "SW3") (pin "1") (pinfunction "1_1") (pintype "passive"))
      (node (ref "SW4") (pin "1") (pinfunction "1_1") (pintype "passive"))
      (node (ref "SW5") (pin "1") (pinfunction "1_1") (pintype "passive"))
      (node (ref "SW6") (pin "1") (pinfunction "1_1") (pintype "passive"))
    )
    (net (code "125") (name "Net-(R8-Pad2)") (class "Default")
      (node (ref "R8") (pin "2") (pinfunction "2_2") (pintype "passive"))
      (node (ref "SW10") (pin "1") (pinfunction "1_1") (pintype "passive"))
      (node (ref "SW7") (pin "1") (pinfunction "1_1") (pintype "passive"))
      (node (ref "SW8") (pin "1") (pinfunction "1_1") (pintype "passive"))
      (node (ref "SW9") (pin "1") (pinfunction "1_1") (pintype "passive"))
    )
    (net (code "126") (name "Net-(R9-Pad2)") (class "Default")
      (node (ref "R9") (pin "2") (pinfunction "2_2") (pintype "passive"))
      (node (ref "SW11") (pin "1") (pinfunction "1_1") (pintype "passive"))
      (node (ref "SW12") (pin "1") (pinfunction "1_1") (pintype "passive"))
      (node (ref "SW13") (pin "1") (pinfunction "1_1") (pintype "passive"))
      (node (ref "SW14") (pin "1") (pinfunction "1_1") (pintype "passive"))
    )
    (net (code "127") (name "Net-(R10-Pad2)") (class "Default")
      (node (ref "R10") (pin "2") (pinfunction "2_2") (pintype "passive"))
      (node (ref "SW15") (pin "1") (pinfunction "1_1") (pintype "passive"))
      (node (ref "SW16") (pin "1") (pinfunction "1_1") (pintype "passive"))
      (node (ref "SW17") (pin "1") (pinfunction "1_1") (pintype "passive"))
      (node (ref "SW18") (pin "1") (pinfunction "1_1") (pintype "passive"))
    )
    (net (code "128") (name "Net-(R11-Pad1)") (class "Default")
      (node (ref "R11") (pin "1") (pinfunction "1_1") (pintype "passive"))
      (node (ref "R18") (pin "1") (pinfunction "1_1") (pintype "passive"))
      (node (ref "SW11") (pin "2") (pinfunction "2_2") (pintype "passive"))
      (node (ref "SW15") (pin "2") (pinfunction "2_2") (pintype "passive"))
      (node (ref "SW3") (pin "2") (pinfunction "2_2") (pintype "passive"))
      (node (ref "SW7") (pin "2") (pinfunction "2_2") (pintype "passive"))
    )
    (net (code "129") (name "Net-(R12-Pad1)") (class "Default")
      (node (ref "R12") (pin "1") (pinfunction "1_1") (pintype "passive"))
      (node (ref "R17") (pin "1") (pinfunction "1_1") (pintype "passive"))
      (node (ref "SW12") (pin "2") (pinfunction "2_2") (pintype "passive"))
      (node (ref "SW16") (pin "2") (pinfunction "2_2") (pintype "passive"))
      (node (ref "SW4") (pin "2") (pinfunction "2_2") (pintype "passive"))
      (node (ref "SW8") (pin "2") (pinfunction "2_2") (pintype "passive"))
    )
    (net (code "130") (name "Net-(R13-Pad1)") (class "Default")
      (node (ref "R13") (pin "1") (pinfunction "1_1") (pintype "passive"))
      (node (ref "R16") (pin "1") (pinfunction "1_1") (pintype "passive"))
      (node (ref "SW13") (pin "2") (pinfunction "2_2") (pintype "passive"))
      (node (ref "SW17") (pin "2") (pinfunction "2_2") (pintype "passive"))
      (node (ref "SW5") (pin "2") (pinfunction "2_2") (pintype "passive"))
      (node (ref "SW9") (pin "2") (pinfunction "2_2") (pintype "passive"))
    )
    (net (code "131") (name "Net-(R14-Pad1)") (class "Default")
      (node (ref "R14") (pin "1") (pinfunction "1_1") (pintype "passive"))
      (node (ref "R15") (pin "1") (pinfunction "1_1") (pintype "passive"))
      (node (ref "SW10") (pin "2") (pinfunction "2_2") (pintype "passive"))
      (node (ref "SW14") (pin "2") (pinfunction "2_2") (pintype "passive"))
      (node (ref "SW18") (pin "2") (pinfunction "2_2") (pintype "passive"))
      (node (ref "SW6") (pin "2") (pinfunction "2_2") (pintype "passive"))
    )
    (net (code "132") (name "Net-(REGULATOR-IN)") (class "Default")
      (node (ref "C4") (pin "2") (pinfunction "2_2") (pintype "passive"))
      (node (ref "H9") (pin "1") (pinfunction "1_1") (pintype "passive"))
      (node (ref "REGULATOR") (pin "1") (pinfunction "IN_1") (pintype "power_in"))
    )
    (net (code "133") (name "VCC") (class "Default")
      (node (ref "ATMEGA32") (pin "10") (pinfunction "VCC_10") (pintype "power_in"))
      (node (ref "ATMEGA32") (pin "30") (pinfunction "AVCC_30") (pintype "power_in"))
      (node (ref "BUZZER") (pin "2") (pinfunction "B_2") (pintype "passive"))
      (node (ref "C5") (pin "2") (pinfunction "2_2") (pintype "passive"))
      (node (ref "D3") (pin "2") (pinfunction "K_2") (pintype "passive"))
      (node (ref "H11") (pin "1") (pinfunction "1_1") (pintype "passive"))
      (node (ref "H5") (pin "1") (pinfunction "1_1") (pintype "passive"))
      (node (ref "H5") (pin "2") (pinfunction "2_2") (pintype "passive"))
      (node (ref "H6") (pin "17") (pinfunction "17_17") (pintype "passive"))
      (node (ref "H6") (pin "18") (pinfunction "18_18") (pintype "passive"))
      (node (ref "H7") (pin "1") (pinfunction "1_1") (pintype "passive"))
      (node (ref "H7") (pin "2") (pinfunction "2_2") (pintype "passive"))
      (node (ref "H8") (pin "17") (pinfunction "17_17") (pintype "passive"))
      (node (ref "H8") (pin "18") (pinfunction "18_18") (pintype "passive"))
      (node (ref "JP3") (pin "2") (pinfunction "2_2") (pintype "passive"))
      (node (ref "JP3") (pin "3") (pinfunction "3_3") (pintype "passive"))
      (node (ref "JP5") (pin "2") (pinfunction "2_2") (pintype "passive"))
      (node (ref "JP5") (pin "3") (pinfunction "3_3") (pintype "passive"))
      (node (ref "LCD") (pin "15") (pinfunction "15_15") (pintype "passive"))
      (node (ref "LCD") (pin "2") (pinfunction "2_2") (pintype "passive"))
      (node (ref "R1") (pin "2") (pinfunction "2_2") (pintype "passive"))
      (node (ref "R21") (pin "2") (pinfunction "2_2") (pintype "passive"))
      (node (ref "R3") (pin "2") (pinfunction "2_2") (pintype "passive"))
      (node (ref "R6") (pin "1") (pinfunction "1_1") (pintype "passive"))
      (node (ref "REGULATOR") (pin "3") (pinfunction "OUT_3") (pintype "power_in"))
      (node (ref "RELAY") (pin "4") (pinfunction "4_4") (pintype "passive"))
    )
    (net (code "134") (name "unconnected-(ATMEGA32-AREF-Pad32)") (class "Default")
      (node (ref "ATMEGA32") (pin "32") (pinfunction "AREF_32") (pintype "power_in"))
    )
    (net (code "135") (name "unconnected-(H7-Pad4)") (class "Default")
      (node (ref "H7") (pin "4") (pinfunction "4_4") (pintype "passive"))
    )
    (net (code "136") (name "unconnected-(H7-Pad6)") (class "Default")
      (node (ref "H7") (pin "6") (pinfunction "6_6") (pintype "passive"))
    )
    (net (code "137") (name "unconnected-(H7-Pad8)") (class "Default")
      (node (ref "H7") (pin "8") (pinfunction "8_8") (pintype "passive"))
    )
    (net (code "138") (name "unconnected-(H7-Pad10)") (class "Default")
      (node (ref "H7") (pin "10") (pinfunction "10_10") (pintype "passive"))
    )
    (net (code "139") (name "unconnected-(H7-Pad12)") (class "Default")
      (node (ref "H7") (pin "12") (pinfunction "12_12") (pintype "passive"))
    )
    (net (code "140") (name "unconnected-(H7-Pad14)") (class "Default")
      (node (ref "H7") (pin "14") (pinfunction "14_14") (pintype "passive"))
    )
    (net (code "141") (name "unconnected-(H7-Pad16)") (class "Default")
      (node (ref "H7") (pin "16") (pinfunction "16_16") (pintype "passive"))
    )
    (net (code "142") (name "unconnected-(H7-Pad18)") (class "Default")
      (node (ref "H7") (pin "18") (pinfunction "18_18") (pintype "passive"))
    )
    (net (code "143") (name "unconnected-(H8-Pad2)") (class "Default")
      (node (ref "H8") (pin "2") (pinfunction "2_2") (pintype "passive"))
    )
    (net (code "144") (name "unconnected-(H8-Pad4)") (class "Default")
      (node (ref "H8") (pin "4") (pinfunction "4_4") (pintype "passive"))
    )
    (net (code "145") (name "unconnected-(H8-Pad6)") (class "Default")
      (node (ref "H8") (pin "6") (pinfunction "6_6") (pintype "passive"))
    )
    (net (code "146") (name "unconnected-(H8-Pad8)") (class "Default")
      (node (ref "H8") (pin "8") (pinfunction "8_8") (pintype "passive"))
    )
    (net (code "147") (name "unconnected-(H8-Pad10)") (class "Default")
      (node (ref "H8") (pin "10") (pinfunction "10_10") (pintype "passive"))
    )
    (net (code "148") (name "unconnected-(H8-Pad12)") (class "Default")
      (node (ref "H8") (pin "12") (pinfunction "12_12") (pintype "passive"))
    )
    (net (code "149") (name "unconnected-(H8-Pad14)") (class "Default")
      (node (ref "H8") (pin "14") (pinfunction "14_14") (pintype "passive"))
    )
    (net (code "150") (name "unconnected-(H8-Pad16)") (class "Default")
      (node (ref "H8") (pin "16") (pinfunction "16_16") (pintype "passive"))
    )
    (net (code "151") (name "unconnected-(LCD-Pad7)") (class "Default")
      (node (ref "LCD") (pin "7") (pinfunction "7_7") (pintype "passive"))
    )
    (net (code "152") (name "unconnected-(LCD-Pad8)") (class "Default")
      (node (ref "LCD") (pin "8") (pinfunction "8_8") (pintype "passive"))
    )
    (net (code "153") (name "unconnected-(LCD-Pad9)") (class "Default")
      (node (ref "LCD") (pin "9") (pinfunction "9_9") (pintype "passive"))
    )
    (net (code "154") (name "unconnected-(LCD-Pad10)") (class "Default")
      (node (ref "LCD") (pin "10") (pinfunction "10_10") (pintype "passive"))
    )
  )
)
